# DMMRectifier_v2.net
KiCad netlist of a schematic drawn in EAGLE
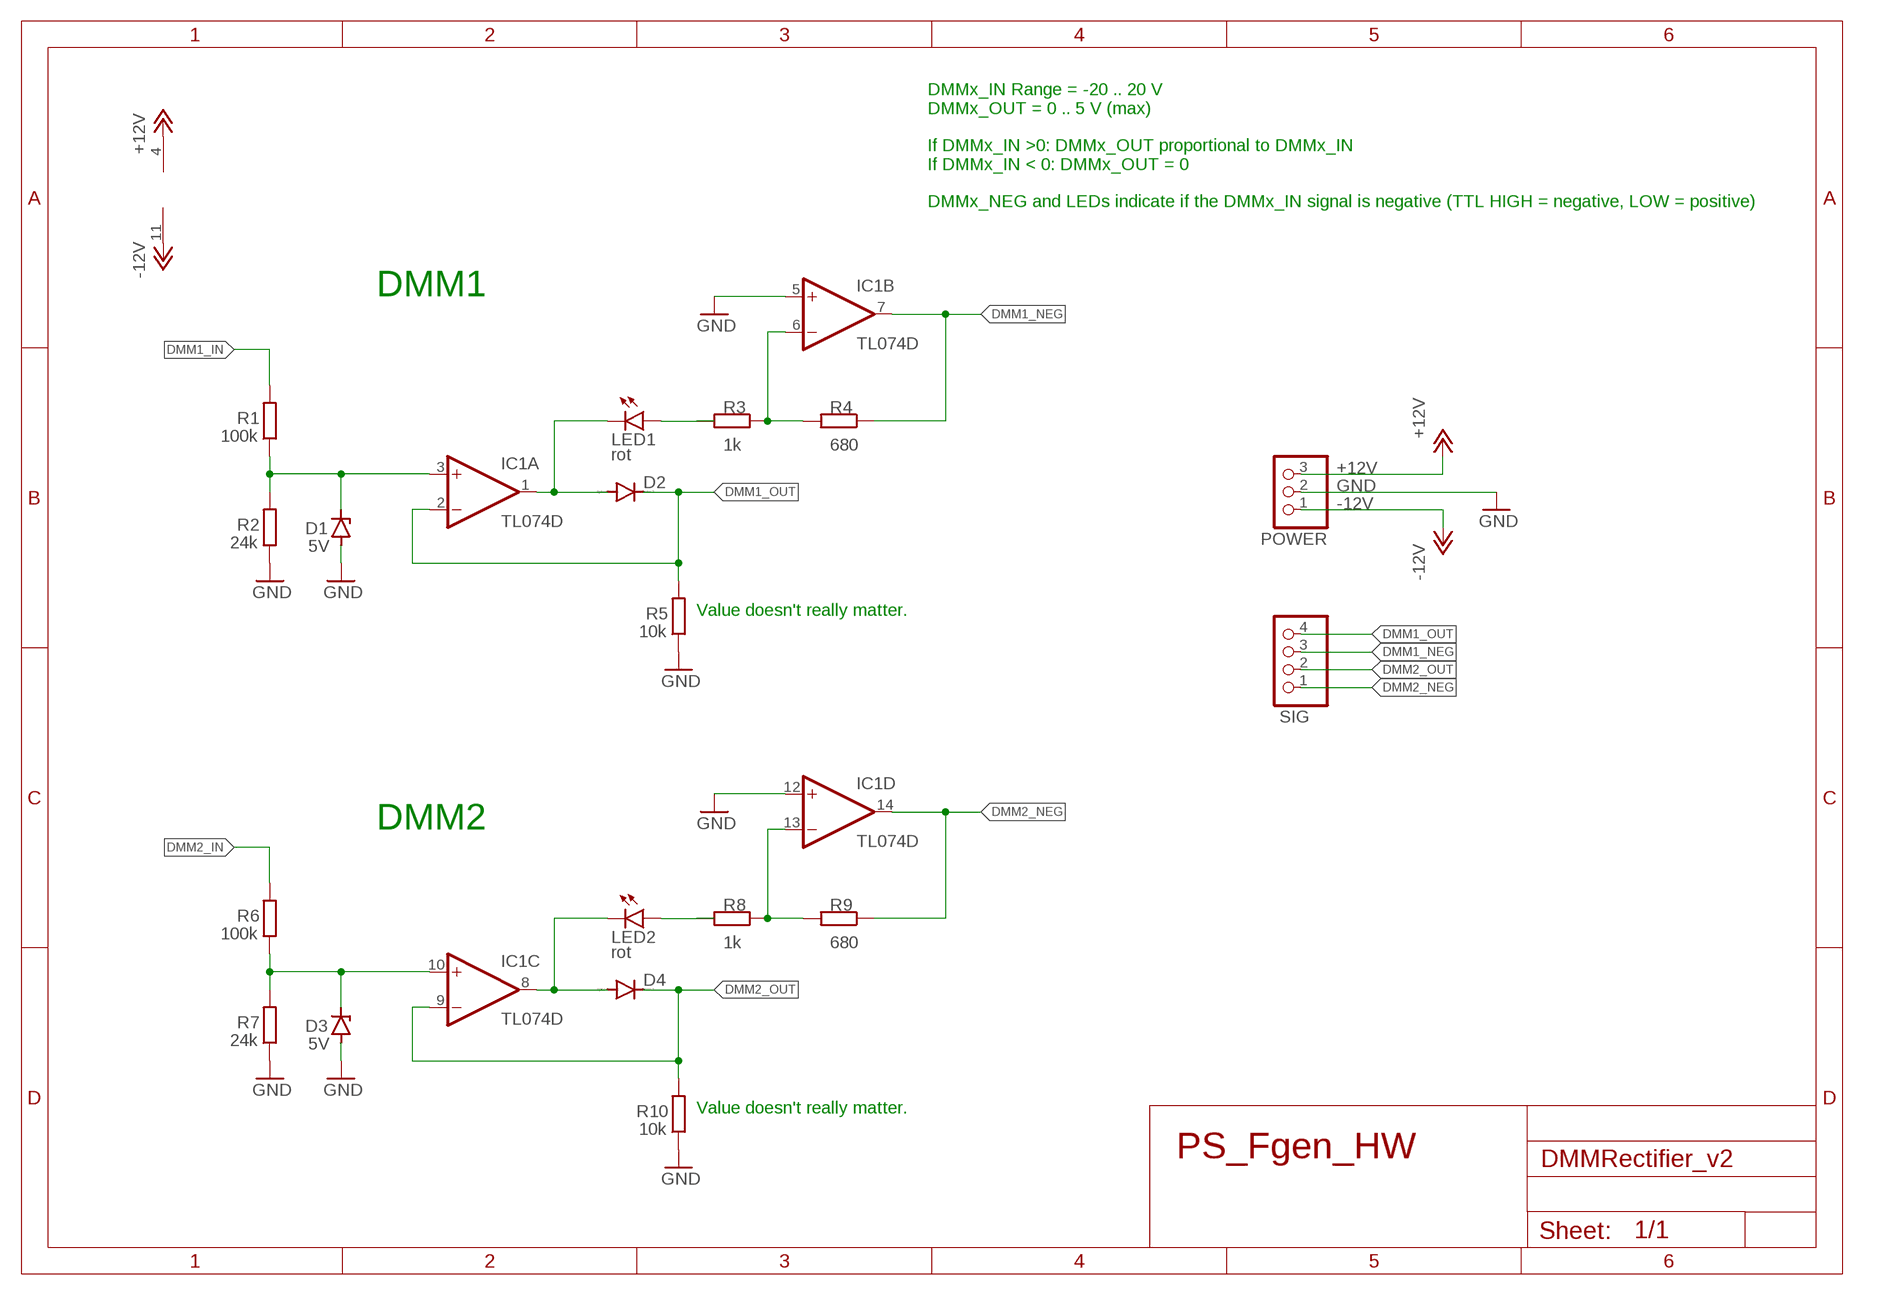
[diagram p0: schematic, sheet 1]

(export (version "E")
  (design (tool "Eeschema 10.0.6"))
  (components
    (comp (ref "D1")
      (value "5V")
      (footprint "eagle-import:SOD80C")
      (libsource (lib "eagle-import") (part "ZENER-DIODESOD80C"))
    )
    (comp (ref "D2")
      (value "DIODE-SOD80C")
      (footprint "eagle-import:SOD80C")
      (libsource (lib "eagle-import") (part "DIODE-SOD80C"))
    )
    (comp (ref "D3")
      (value "5V")
      (footprint "eagle-import:SOD80C")
      (libsource (lib "eagle-import") (part "ZENER-DIODESOD80C"))
    )
    (comp (ref "D4")
      (value "DIODE-SOD80C")
      (footprint "eagle-import:SOD80C")
      (libsource (lib "eagle-import") (part "DIODE-SOD80C"))
    )
    (comp (ref "IC1")
      (value "TL074D")
      (footprint "eagle-import:SO14")
      (fields (field (name "SPICEPREFIX") "I"))
      (libsource (lib "eagle-import") (part "TL074D"))
    )
    (comp (ref "LED1")
      (value "rot")
      (footprint "eagle-import:CHIPLED_0603")
      (libsource (lib "eagle-import") (part "LEDCHIPLED_0603"))
    )
    (comp (ref "LED2")
      (value "rot")
      (footprint "eagle-import:CHIPLED_0603")
      (libsource (lib "eagle-import") (part "LEDCHIPLED_0603"))
    )
    (comp (ref "POWER")
      (value "PINHD-1X3")
      (footprint "eagle-import:1X03")
      (libsource (lib "eagle-import") (part "PINHD-1X3"))
    )
    (comp (ref "R1")
      (value "100k")
      (footprint "eagle-import:R0805")
      (libsource (lib "eagle-import") (part "R-EU_R0805"))
    )
    (comp (ref "R2")
      (value "24k")
      (footprint "eagle-import:R0805")
      (libsource (lib "eagle-import") (part "R-EU_R0805"))
    )
    (comp (ref "R3")
      (value "1k")
      (footprint "eagle-import:R0805")
      (libsource (lib "eagle-import") (part "R-EU_R0805"))
    )
    (comp (ref "R4")
      (value "680")
      (footprint "eagle-import:R0805")
      (libsource (lib "eagle-import") (part "R-EU_R0805"))
    )
    (comp (ref "R5")
      (value "10k")
      (footprint "eagle-import:R0805")
      (libsource (lib "eagle-import") (part "R-EU_R0805"))
    )
    (comp (ref "R6")
      (value "100k")
      (footprint "eagle-import:R0805")
      (libsource (lib "eagle-import") (part "R-EU_R0805"))
    )
    (comp (ref "R7")
      (value "24k")
      (footprint "eagle-import:R0805")
      (libsource (lib "eagle-import") (part "R-EU_R0805"))
    )
    (comp (ref "R8")
      (value "1k")
      (footprint "eagle-import:R0805")
      (libsource (lib "eagle-import") (part "R-EU_R0805"))
    )
    (comp (ref "R9")
      (value "680")
      (footprint "eagle-import:R0805")
      (libsource (lib "eagle-import") (part "R-EU_R0805"))
    )
    (comp (ref "R10")
      (value "10k")
      (footprint "eagle-import:R0805")
      (libsource (lib "eagle-import") (part "R-EU_R0805"))
    )
    (comp (ref "SIG")
      (value "PINHD-1X4")
      (footprint "eagle-import:1X04")
      (libsource (lib "eagle-import") (part "PINHD-1X4"))
    )
  )
  (nets
    (net (code "1") (name "+12V") (class "Default")
      (node (ref "IC1") (pin "4") (pinfunction "V+_4") (pintype "power_in"))
      (node (ref "POWER") (pin "3") (pinfunction "3_3") (pintype "passive"))
    )
    (net (code "2") (name "-12V") (class "Default")
      (node (ref "IC1") (pin "11") (pinfunction "V-_11") (pintype "power_in"))
      (node (ref "POWER") (pin "1") (pinfunction "1_1") (pintype "passive"))
    )
    (net (code "3") (name "DMM1_IN") (class "Default")
      (node (ref "R1") (pin "2") (pinfunction "2_2") (pintype "passive"))
    )
    (net (code "4") (name "DMM1_NEG") (class "Default")
      (node (ref "IC1") (pin "7") (pinfunction "OUT_7") (pintype "output"))
      (node (ref "R4") (pin "1") (pinfunction "1_1") (pintype "passive"))
      (node (ref "SIG") (pin "3") (pinfunction "3_3") (pintype "passive"))
    )
    (net (code "5") (name "DMM1_OUT") (class "Default")
      (node (ref "D2") (pin "C") (pinfunction "C_C") (pintype "passive"))
      (node (ref "IC1") (pin "2") (pinfunction "-IN_2") (pintype "input"))
      (node (ref "R5") (pin "2") (pinfunction "2_2") (pintype "passive"))
      (node (ref "SIG") (pin "4") (pinfunction "4_4") (pintype "passive"))
    )
    (net (code "6") (name "DMM2_IN") (class "Default")
      (node (ref "R6") (pin "2") (pinfunction "2_2") (pintype "passive"))
    )
    (net (code "7") (name "DMM2_NEG") (class "Default")
      (node (ref "IC1") (pin "14") (pinfunction "OUT_14") (pintype "output"))
      (node (ref "R9") (pin "1") (pinfunction "1_1") (pintype "passive"))
      (node (ref "SIG") (pin "1") (pinfunction "1_1") (pintype "passive"))
    )
    (net (code "8") (name "DMM2_OUT") (class "Default")
      (node (ref "D4") (pin "C") (pinfunction "C_C") (pintype "passive"))
      (node (ref "IC1") (pin "9") (pinfunction "-IN_9") (pintype "input"))
      (node (ref "R10") (pin "2") (pinfunction "2_2") (pintype "passive"))
      (node (ref "SIG") (pin "2") (pinfunction "2_2") (pintype "passive"))
    )
    (net (code "9") (name "GND") (class "Default")
      (node (ref "D1") (pin "A") (pinfunction "A_A") (pintype "passive"))
      (node (ref "D3") (pin "A") (pinfunction "A_A") (pintype "passive"))
      (node (ref "IC1") (pin "12") (pinfunction "+IN_12") (pintype "input"))
      (node (ref "IC1") (pin "5") (pinfunction "+IN_5") (pintype "input"))
      (node (ref "POWER") (pin "2") (pinfunction "2_2") (pintype "passive"))
      (node (ref "R10") (pin "1") (pinfunction "1_1") (pintype "passive"))
      (node (ref "R2") (pin "1") (pinfunction "1_1") (pintype "passive"))
      (node (ref "R5") (pin "1") (pinfunction "1_1") (pintype "passive"))
      (node (ref "R7") (pin "1") (pinfunction "1_1") (pintype "passive"))
    )
    (net (code "10") (name "Net-(IC1A-+IN)") (class "Default")
      (node (ref "D1") (pin "C") (pinfunction "C_C") (pintype "passive"))
      (node (ref "IC1") (pin "3") (pinfunction "+IN_3") (pintype "input"))
      (node (ref "R1") (pin "1") (pinfunction "1_1") (pintype "passive"))
      (node (ref "R2") (pin "2") (pinfunction "2_2") (pintype "passive"))
    )
    (net (code "11") (name "Net-(IC1A-OUT)") (class "Default")
      (node (ref "D2") (pin "A") (pinfunction "A_A") (pintype "passive"))
      (node (ref "IC1") (pin "1") (pinfunction "OUT_1") (pintype "output"))
      (node (ref "LED1") (pin "C") (pinfunction "C_C") (pintype "passive"))
    )
    (net (code "12") (name "Net-(IC1B--IN)") (class "Default")
      (node (ref "IC1") (pin "6") (pinfunction "-IN_6") (pintype "input"))
      (node (ref "R3") (pin "1") (pinfunction "1_1") (pintype "passive"))
      (node (ref "R4") (pin "2") (pinfunction "2_2") (pintype "passive"))
    )
    (net (code "13") (name "Net-(IC1C-+IN)") (class "Default")
      (node (ref "D3") (pin "C") (pinfunction "C_C") (pintype "passive"))
      (node (ref "IC1") (pin "10") (pinfunction "+IN_10") (pintype "input"))
      (node (ref "R6") (pin "1") (pinfunction "1_1") (pintype "passive"))
      (node (ref "R7") (pin "2") (pinfunction "2_2") (pintype "passive"))
    )
    (net (code "14") (name "Net-(IC1C-OUT)") (class "Default")
      (node (ref "D4") (pin "A") (pinfunction "A_A") (pintype "passive"))
      (node (ref "IC1") (pin "8") (pinfunction "OUT_8") (pintype "output"))
      (node (ref "LED2") (pin "C") (pinfunction "C_C") (pintype "passive"))
    )
    (net (code "15") (name "Net-(IC1D--IN)") (class "Default")
      (node (ref "IC1") (pin "13") (pinfunction "-IN_13") (pintype "input"))
      (node (ref "R8") (pin "1") (pinfunction "1_1") (pintype "passive"))
      (node (ref "R9") (pin "2") (pinfunction "2_2") (pintype "passive"))
    )
    (net (code "16") (name "Net-(LED1-PadA)") (class "Default")
      (node (ref "LED1") (pin "A") (pinfunction "A_A") (pintype "passive"))
      (node (ref "R3") (pin "2") (pinfunction "2_2") (pintype "passive"))
    )
    (net (code "17") (name "Net-(LED2-PadA)") (class "Default")
      (node (ref "LED2") (pin "A") (pinfunction "A_A") (pintype "passive"))
      (node (ref "R8") (pin "2") (pinfunction "2_2") (pintype "passive"))
    )
  )
)
